# cc2530.net
KiCad netlist of a schematic drawn in Altium Designer
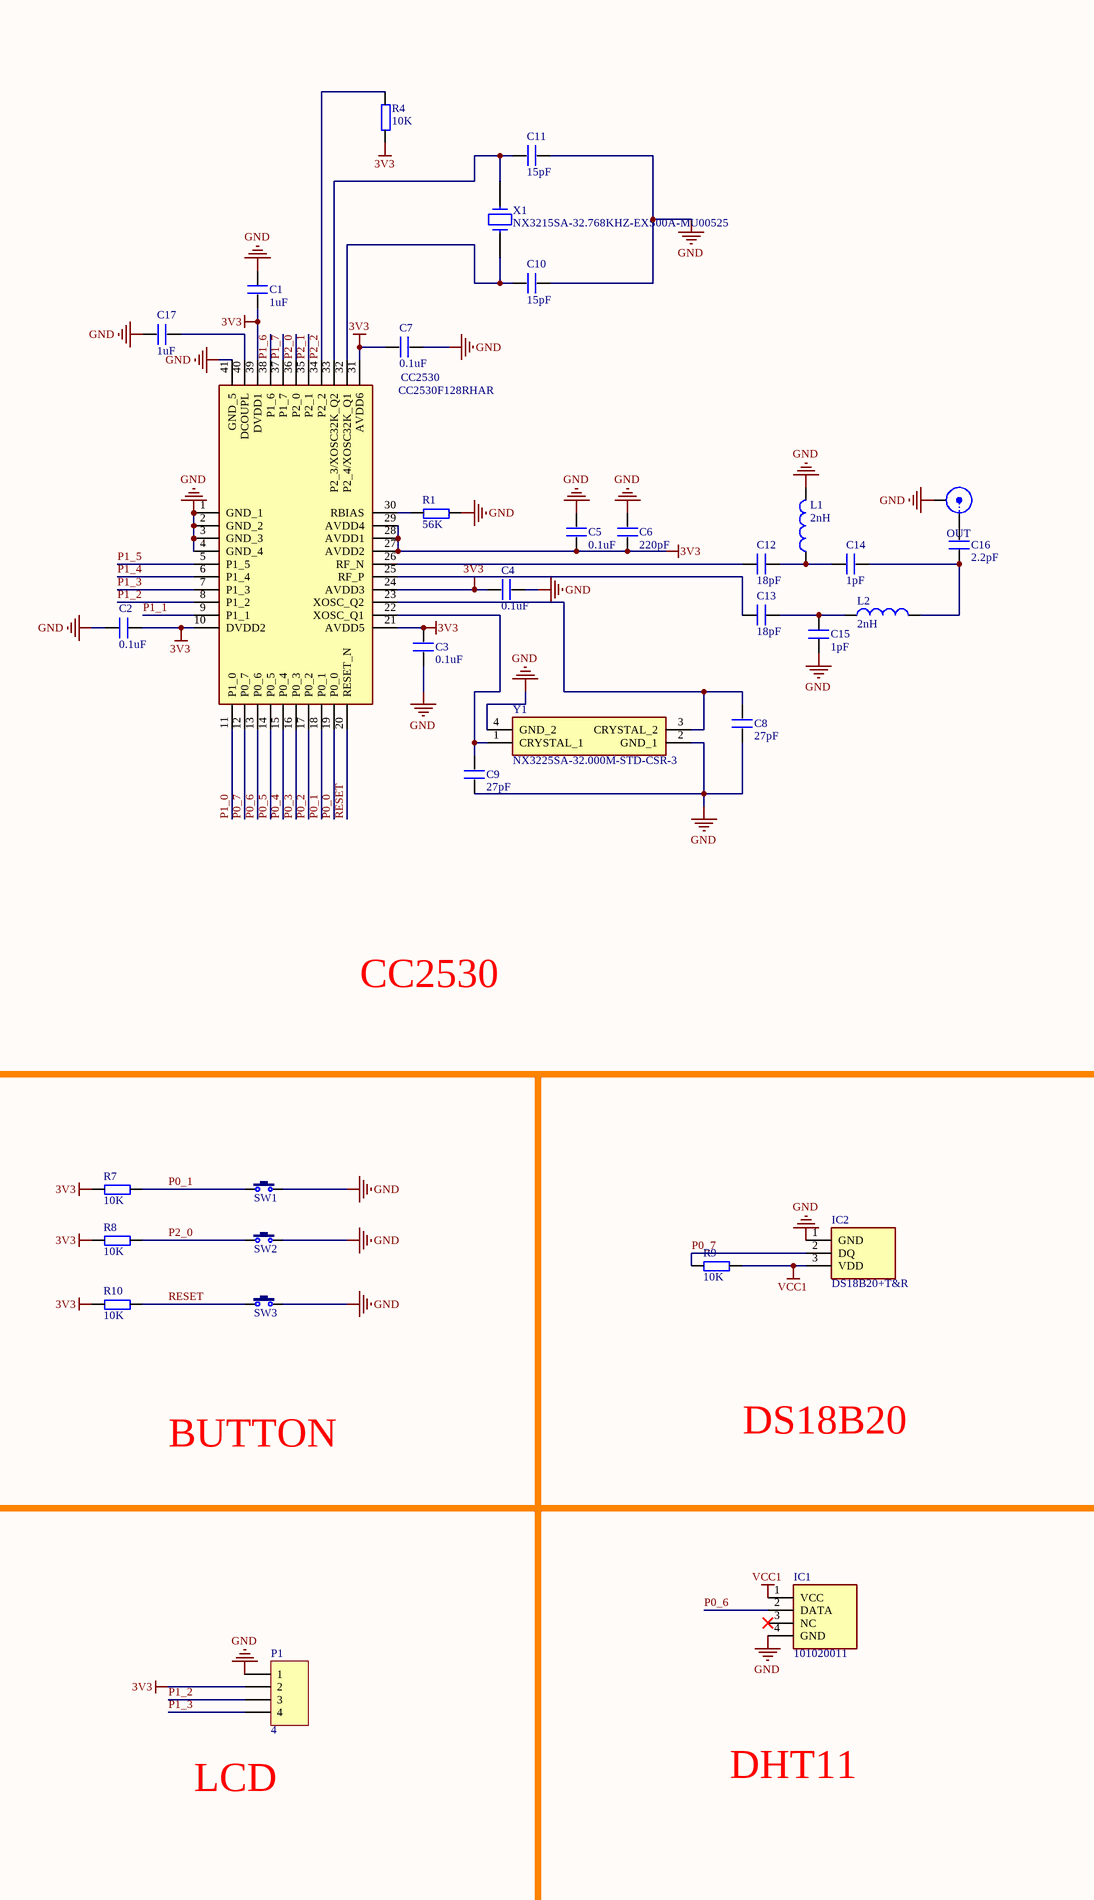
[diagram p0: cc2530.SchDoc, left]
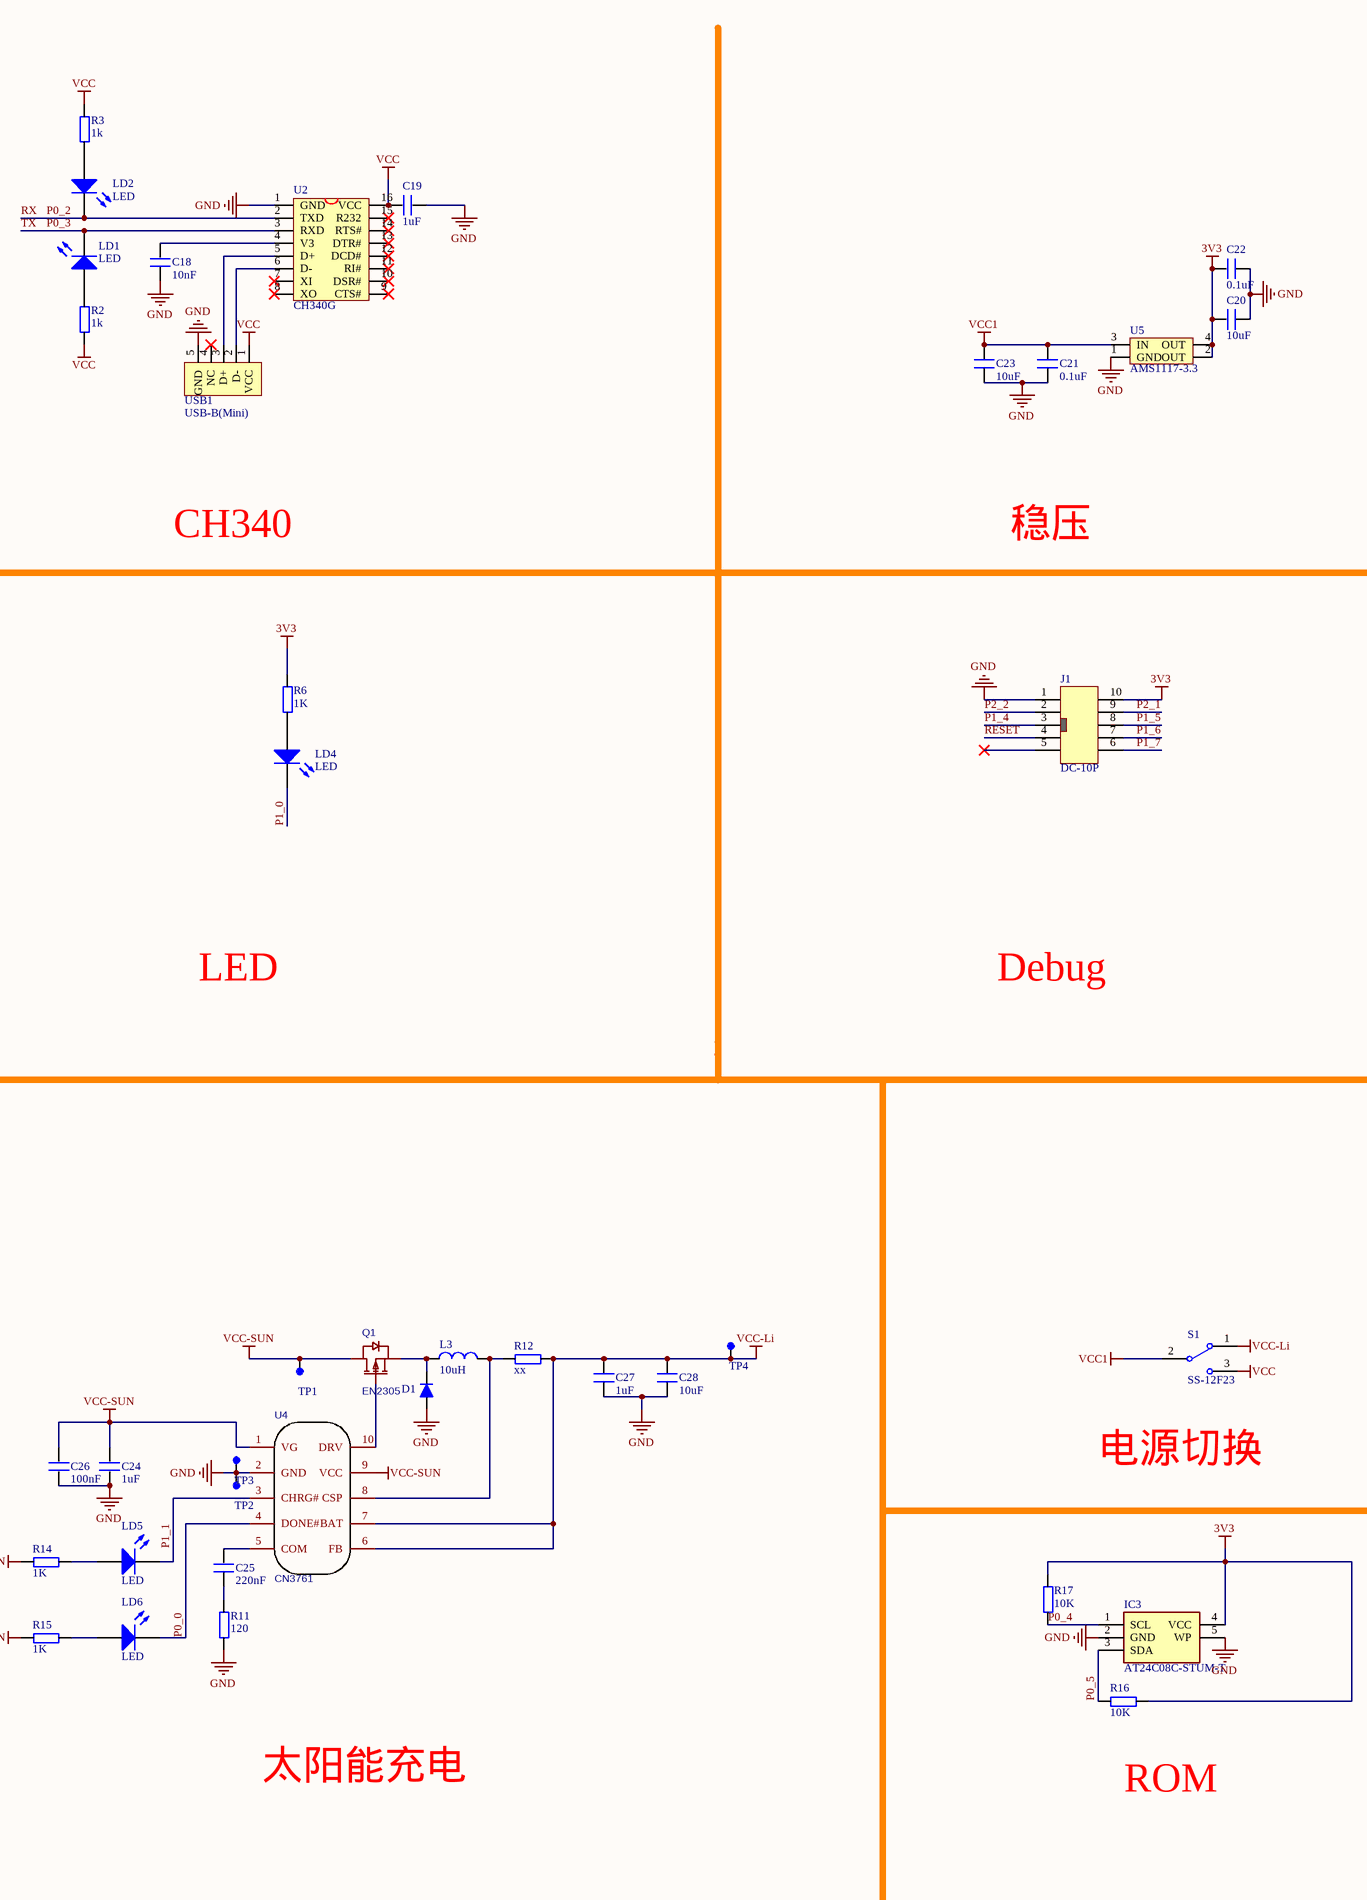
[diagram p1: cc2530.SchDoc, right]

(export (version "E")
  (design (tool "Eeschema 10.0.6"))
  (components
    (comp (ref "C1")
      (value "1uF")
      (footprint "0402")
      (description "Capacitor")
      (libsource (lib "MYLIB") (part "C"))
    )
    (comp (ref "C2")
      (value "0.1uF")
      (footprint "0402")
      (description "Capacitor")
      (libsource (lib "MYLIB") (part "C"))
    )
    (comp (ref "C3")
      (value "0.1uF")
      (footprint "0402")
      (description "Capacitor")
      (libsource (lib "MYLIB") (part "C"))
    )
    (comp (ref "C4")
      (value "0.1uF")
      (footprint "0402")
      (description "Capacitor")
      (libsource (lib "MYLIB") (part "C"))
    )
    (comp (ref "C5")
      (value "0.1uF")
      (footprint "0402")
      (description "Capacitor")
      (libsource (lib "MYLIB") (part "C"))
    )
    (comp (ref "C6")
      (value "220pF")
      (footprint "0402")
      (description "Capacitor")
      (libsource (lib "MYLIB") (part "C"))
    )
    (comp (ref "C7")
      (value "0.1uF")
      (footprint "0402")
      (description "Capacitor")
      (libsource (lib "MYLIB") (part "C"))
    )
    (comp (ref "C8")
      (value "27pF")
      (footprint "0603C")
      (description "Capacitor")
      (libsource (lib "MYLIB") (part "C"))
    )
    (comp (ref "C9")
      (value "27pF")
      (footprint "0603C")
      (description "Capacitor")
      (libsource (lib "MYLIB") (part "C"))
    )
    (comp (ref "C10")
      (value "15pF")
      (footprint "0603C")
      (description "Capacitor")
      (libsource (lib "MYLIB") (part "C"))
    )
    (comp (ref "C11")
      (value "15pF")
      (footprint "0603C")
      (description "Capacitor")
      (libsource (lib "MYLIB") (part "C"))
    )
    (comp (ref "C12")
      (value "18pF")
      (footprint "0402")
      (description "Capacitor")
      (libsource (lib "MYLIB") (part "C"))
    )
    (comp (ref "C13")
      (value "18pF")
      (footprint "0402")
      (description "Capacitor")
      (libsource (lib "MYLIB") (part "C"))
    )
    (comp (ref "C14")
      (value "1pF")
      (footprint "0402")
      (description "Capacitor")
      (libsource (lib "MYLIB") (part "C"))
    )
    (comp (ref "C15")
      (value "1pF")
      (footprint "0402")
      (description "Capacitor")
      (libsource (lib "MYLIB") (part "C"))
    )
    (comp (ref "C16")
      (value "2.2pF")
      (footprint "0402")
      (description "Capacitor")
      (libsource (lib "MYLIB") (part "C"))
    )
    (comp (ref "C17")
      (value "1uF")
      (footprint "0402")
      (description "Capacitor")
      (libsource (lib "MYLIB") (part "C"))
    )
    (comp (ref "C18")
      (value "10nF")
      (footprint "0603C")
      (description "Capacitor")
      (libsource (lib "MYLIB") (part "C"))
    )
    (comp (ref "C19")
      (value "1uF")
      (footprint "0603C")
      (description "Capacitor")
      (libsource (lib "MYLIB") (part "C"))
    )
    (comp (ref "C20")
      (value "10uF")
      (footprint "0603C")
      (description "Capacitor")
      (libsource (lib "MYLIB") (part "C"))
    )
    (comp (ref "C21")
      (value "0.1uF")
      (footprint "0603C")
      (description "Capacitor")
      (libsource (lib "MYLIB") (part "C"))
    )
    (comp (ref "C22")
      (value "0.1uF")
      (footprint "0603C")
      (description "Capacitor")
      (libsource (lib "MYLIB") (part "C"))
    )
    (comp (ref "C23")
      (value "10uF")
      (footprint "0603C")
      (description "Capacitor")
      (libsource (lib "MYLIB") (part "C"))
    )
    (comp (ref "C24")
      (value "1uF")
      (footprint "0603C")
      (description "Capacitor")
      (libsource (lib "MYLIB") (part "C"))
    )
    (comp (ref "C25")
      (value "220nF")
      (footprint "0603C")
      (description "Capacitor")
      (libsource (lib "MYLIB") (part "C"))
    )
    (comp (ref "C26")
      (value "100nF")
      (footprint "0603C")
      (description "Capacitor")
      (libsource (lib "MYLIB") (part "C"))
    )
    (comp (ref "C27")
      (value "1uF")
      (footprint "0603C")
      (description "Capacitor")
      (libsource (lib "MYLIB") (part "C"))
    )
    (comp (ref "C28")
      (value "10uF")
      (footprint "0603C")
      (description "Capacitor")
      (libsource (lib "MYLIB") (part "C"))
    )
    (comp (ref "CC2530")
      (value "CC2530F128RHAR")
      (footprint "MYLIB:QFN50P600X600X100-41N-D")
      (description "Integrated Circuit")
      (fields (field (name "MOUSER PART NUMBER") "595-CC2530F128RHAR"))
      (libsource (lib "*") (part "CC2530F128RHAR"))
    )
    (comp (ref "D1")
      (value "D")
      (footprint "D-SMA")
      (description "二极管")
      (libsource (lib "xuxuxu") (part "Diode"))
    )
    (comp (ref "IC1")
      (value "101020011")
      (footprint "MYLIB:HDRV4W80P0X254_1X4_1200X500X1550P")
      (description "Integrated Circuit")
      (fields (field (name "MOUSER PART NUMBER") "713-101020011"))
      (libsource (lib "*") (part "101020011"))
    )
    (comp (ref "IC2")
      (value "DS18B20+T&R")
      (footprint "MYLIB:DS18B20TR")
      (description "Integrated Circuit")
      (fields (field (name "MOUSER PART NUMBER") "700-DS18B20T&R"))
      (libsource (lib "*") (part "DS18B20+T&R"))
    )
    (comp (ref "IC3")
      (value "AT24C08C-STUM-T")
      (footprint "MYLIB:SOT95P280X100-5N")
      (description "Integrated Circuit")
      (fields (field (name "MOUSER PART NUMBER") "556-AT24C08C-STUM-T"))
      (libsource (lib "*") (part "AT24C08C-STUM-T"))
    )
    (comp (ref "J1") (value "DC-10P") (footprint "DC-10P") (libsource (lib "xuxuxu") (part "DC-10P")))
    (comp (ref "L1")
      (value "2nH")
      (footprint "0402")
      (description "Inductor")
      (fields (field (name "PUBLISHER") "Altium Limited"))
      (libsource (lib "MYLIB") (part "Inductor"))
    )
    (comp (ref "L2")
      (value "2nH")
      (footprint "0402")
      (description "Inductor")
      (fields (field (name "PUBLISHER") "Altium Limited"))
      (libsource (lib "MYLIB") (part "Inductor"))
    )
    (comp (ref "L3") (value "10uH") (footprint "L-6.5mm") (libsource (lib "xuxuxu") (part "Inductor")))
    (comp (ref "LD1")
      (value "LED")
      (footprint "SMDLED")
      (description "Typical RED, GREEN, YELLOW, AMBER GaAs LED")
      (fields (field (name "PUBLISHER") "Altium Limited"))
      (libsource (lib "MYLIB") (part "LED"))
    )
    (comp (ref "LD2")
      (value "LED")
      (footprint "SMDLED")
      (description "Typical RED, GREEN, YELLOW, AMBER GaAs LED")
      (fields (field (name "PUBLISHER") "Altium Limited"))
      (libsource (lib "MYLIB") (part "LED"))
    )
    (comp (ref "LD4")
      (value "LED")
      (footprint "SMDLED")
      (description "Typical RED, GREEN, YELLOW, AMBER GaAs LED")
      (fields (field (name "PUBLISHER") "Altium Limited"))
      (libsource (lib "MYLIB") (part "LED"))
    )
    (comp (ref "LD5")
      (value "LED")
      (footprint "SMDLED")
      (description "Typical RED, GREEN, YELLOW, AMBER GaAs LED")
      (fields (field (name "PUBLISHER") "Altium Limited"))
      (libsource (lib "MYLIB") (part "LED"))
    )
    (comp (ref "LD6")
      (value "LED")
      (footprint "SMDLED")
      (description "Typical RED, GREEN, YELLOW, AMBER GaAs LED")
      (fields (field (name "PUBLISHER") "Altium Limited"))
      (libsource (lib "MYLIB") (part "LED"))
    )
    (comp (ref "OUT")
      (value "SMA")
      (footprint "SMA")
      (description "SMA Connector")
      (libsource (lib "MYLIB") (part "SMA"))
    )
    (comp (ref "P1")
      (value "4")
      (footprint "HDR1X4")
      (description "Header, 4-Pin")
      (fields (field (name "PUBLISHER") "Altium Limited"))
      (libsource (lib "MYLIB") (part "Header 4"))
    )
    (comp (ref "Q1")
      (value "EN2305")
      (footprint "CN2305")
      (fields (field (name "BOM_SUPPLIER PART") "C967035") (field (name "CONTRIBUTOR") "LCSC"))
      (libsource (lib "MYLIB") (part "EN2305"))
    )
    (comp (ref "R1")
      (value "56K")
      (footprint "0402")
      (description "Resistor")
      (libsource (lib "MYLIB") (part "Resistor"))
    )
    (comp (ref "R2")
      (value "1k")
      (footprint "0603R")
      (description "Resistor")
      (libsource (lib "MYLIB") (part "Resistor"))
    )
    (comp (ref "R3")
      (value "1k")
      (footprint "0603R")
      (description "Resistor")
      (libsource (lib "MYLIB") (part "Resistor"))
    )
    (comp (ref "R4")
      (value "10K")
      (footprint "0603R")
      (description "Resistor")
      (libsource (lib "MYLIB") (part "Resistor"))
    )
    (comp (ref "R6")
      (value "1K")
      (footprint "0603R")
      (description "Resistor")
      (libsource (lib "MYLIB") (part "Resistor"))
    )
    (comp (ref "R7")
      (value "10K")
      (footprint "0603R")
      (description "Resistor")
      (libsource (lib "MYLIB") (part "Resistor"))
    )
    (comp (ref "R8")
      (value "10K")
      (footprint "0603R")
      (description "Resistor")
      (libsource (lib "MYLIB") (part "Resistor"))
    )
    (comp (ref "R9")
      (value "10K")
      (footprint "0603R")
      (description "Resistor")
      (libsource (lib "MYLIB") (part "Resistor"))
    )
    (comp (ref "R10")
      (value "10K")
      (footprint "0603R")
      (description "Resistor")
      (libsource (lib "MYLIB") (part "Resistor"))
    )
    (comp (ref "R11")
      (value "120")
      (footprint "0603R")
      (description "Resistor")
      (libsource (lib "MYLIB") (part "Resistor"))
    )
    (comp (ref "R12")
      (value "xx")
      (footprint "0603R")
      (description "Resistor")
      (libsource (lib "MYLIB") (part "Resistor"))
    )
    (comp (ref "R14")
      (value "1K")
      (footprint "0402")
      (description "Resistor")
      (libsource (lib "MYLIB") (part "Resistor"))
    )
    (comp (ref "R15")
      (value "1K")
      (footprint "0402")
      (description "Resistor")
      (libsource (lib "MYLIB") (part "Resistor"))
    )
    (comp (ref "R16")
      (value "10K")
      (footprint "0603R")
      (description "Resistor")
      (libsource (lib "MYLIB") (part "Resistor"))
    )
    (comp (ref "R17")
      (value "10K")
      (footprint "0603R")
      (description "Resistor")
      (libsource (lib "MYLIB") (part "Resistor"))
    )
    (comp (ref "S1")
      (value "SS-12F23")
      (footprint "MSK-12C01-07")
      (description "1路波动开关")
      (fields (field (name "版权归属") "源创客"))
      (libsource (lib "MYLIB") (part "SSW-1P"))
    )
    (comp (ref "SW1")
      (value "3x6x5")
      (footprint "TSW SMD-3*6*2.5")
      (description "3x6轻触开关")
      (fields (field (name "版权归属") "源创客"))
      (libsource (lib "MYLIB") (part "TSW 3x6"))
    )
    (comp (ref "SW2")
      (value "3x6x5")
      (footprint "TSW SMD-3*6*2.5")
      (description "3x6轻触开关")
      (fields (field (name "版权归属") "源创客"))
      (libsource (lib "MYLIB") (part "TSW 3x6"))
    )
    (comp (ref "SW3")
      (value "3x6x5")
      (footprint "TSW SMD-3*6*2.5")
      (description "3x6轻触开关")
      (fields (field (name "版权归属") "源创客"))
      (libsource (lib "MYLIB") (part "TSW 3x6"))
    )
    (comp (ref "TP1") (value "test point") (footprint "TP") (libsource (lib "xuxuxu") (part "TP")))
    (comp (ref "TP2") (value "test point") (footprint "TP") (libsource (lib "xuxuxu") (part "TP")))
    (comp (ref "TP3") (value "test point") (footprint "TP") (libsource (lib "xuxuxu") (part "TP")))
    (comp (ref "TP4") (value "test point") (footprint "TP") (libsource (lib "xuxuxu") (part "TP")))
    (comp (ref "U2")
      (value "CH340G")
      (footprint "SOP16M")
      (description "USB2UART")
      (libsource (lib "MYLIB") (part "CH340G"))
    )
    (comp (ref "U4")
      (value "CN3761")
      (footprint "CN3761")
      (fields (field (name "BOM_SUPPLIER PART") "C41308"))
      (libsource (lib "MYLIB") (part "CN3761_1"))
    )
    (comp (ref "U5") (value "AMS1117-3.3") (footprint "AMS1117") (libsource (lib "MYLIB") (part "AMS1117")))
    (comp (ref "USB1")
      (value "USB-B(Mini)")
      (footprint "USB/SM0.8-6H5")
      (libsource (lib "MYLIB") (part "USB5_1"))
    )
    (comp (ref "X1")
      (value "NX3215SA-32.768KHZ-EXS00A-MU00525")
      (footprint "XTAL_2SM_3R2X1R5")
      (description "Crystal")
      (libsource (lib "MYLIB") (part "XTAL"))
    )
    (comp (ref "Y1")
      (value "NX3225SA-32.000M-STD-CSR-3")
      (footprint "MYLIB:NX3225SA12000MSTDCSR3")
      (description "Crystal or Oscillator")
      (fields (field (name "MANUFACTURER_PART_NUMBER") "NX3225SA-12.000M-STD-CSR-3"))
      (libsource (lib "*") (part "NX3225SA-12.000M-STD-CSR-3"))
    )
  )
  (nets
    (net (code "1") (name "/P0_0") (class "Default")
      (node (ref "CC2530") (pin "19") (pinfunction "P0_0_19") (pintype "passive"))
      (node (ref "LD6") (pin "2") (pinfunction "K_2") (pintype "passive"))
      (node (ref "U4") (pin "4") (pinfunction "DONE#_4") (pintype "passive"))
    )
    (net (code "2") (name "/P0_1") (class "Default")
      (node (ref "CC2530") (pin "18") (pinfunction "P0_1_18") (pintype "passive"))
      (node (ref "R7") (pin "2") (pintype "passive"))
      (node (ref "SW1") (pin "1") (pinfunction "1_1") (pintype "passive"))
    )
    (net (code "3") (name "/P0_2") (class "Default")
      (node (ref "CC2530") (pin "17") (pinfunction "P0_2_17") (pintype "passive"))
      (node (ref "LD2") (pin "2") (pinfunction "K_2") (pintype "passive"))
      (node (ref "U2") (pin "2") (pinfunction "TXD_2") (pintype "passive"))
    )
    (net (code "4") (name "/P0_3") (class "Default")
      (node (ref "CC2530") (pin "16") (pinfunction "P0_3_16") (pintype "passive"))
      (node (ref "LD1") (pin "2") (pinfunction "K_2") (pintype "passive"))
      (node (ref "U2") (pin "3") (pinfunction "RXD_3") (pintype "passive"))
    )
    (net (code "5") (name "/P0_4") (class "Default")
      (node (ref "CC2530") (pin "15") (pinfunction "P0_4_15") (pintype "passive"))
      (node (ref "IC3") (pin "1") (pinfunction "SCL_1") (pintype "passive"))
      (node (ref "R17") (pin "1") (pintype "passive"))
    )
    (net (code "6") (name "/P0_5") (class "Default")
      (node (ref "CC2530") (pin "14") (pinfunction "P0_5_14") (pintype "passive"))
      (node (ref "IC3") (pin "3") (pinfunction "SDA_3") (pintype "passive"))
      (node (ref "R16") (pin "1") (pintype "passive"))
    )
    (net (code "7") (name "/P0_6") (class "Default")
      (node (ref "CC2530") (pin "13") (pinfunction "P0_6_13") (pintype "passive"))
      (node (ref "IC1") (pin "2") (pinfunction "DATA_2") (pintype "passive"))
    )
    (net (code "8") (name "/P0_7") (class "Default")
      (node (ref "CC2530") (pin "12") (pinfunction "P0_7_12") (pintype "passive"))
      (node (ref "IC2") (pin "2") (pinfunction "DQ_2") (pintype "passive"))
      (node (ref "R9") (pin "1") (pintype "passive"))
    )
    (net (code "9") (name "/P1_0") (class "Default")
      (node (ref "CC2530") (pin "11") (pinfunction "P1_0_11") (pintype "passive"))
      (node (ref "LD4") (pin "2") (pinfunction "K_2") (pintype "passive"))
    )
    (net (code "10") (name "/P1_1") (class "Default")
      (node (ref "CC2530") (pin "9") (pinfunction "P1_1_9") (pintype "passive"))
      (node (ref "LD5") (pin "2") (pinfunction "K_2") (pintype "passive"))
      (node (ref "U4") (pin "3") (pinfunction "CHRG#_3") (pintype "passive"))
    )
    (net (code "11") (name "/P1_2") (class "Default")
      (node (ref "CC2530") (pin "8") (pinfunction "P1_2_8") (pintype "passive"))
      (node (ref "P1") (pin "3") (pinfunction "3_3") (pintype "passive"))
    )
    (net (code "12") (name "/P1_3") (class "Default")
      (node (ref "CC2530") (pin "7") (pinfunction "P1_3_7") (pintype "passive"))
      (node (ref "P1") (pin "4") (pinfunction "4_4") (pintype "passive"))
    )
    (net (code "13") (name "/P1_4") (class "Default")
      (node (ref "CC2530") (pin "6") (pinfunction "P1_4_6") (pintype "passive"))
      (node (ref "J1") (pin "3") (pinfunction "3_3") (pintype "passive"))
    )
    (net (code "14") (name "/P1_5") (class "Default")
      (node (ref "CC2530") (pin "5") (pinfunction "P1_5_5") (pintype "passive"))
      (node (ref "J1") (pin "8") (pinfunction "8_8") (pintype "passive"))
    )
    (net (code "15") (name "/P1_6") (class "Default")
      (node (ref "CC2530") (pin "38") (pinfunction "P1_6_38") (pintype "passive"))
      (node (ref "J1") (pin "7") (pinfunction "7_7") (pintype "passive"))
    )
    (net (code "16") (name "/P1_7") (class "Default")
      (node (ref "CC2530") (pin "37") (pinfunction "P1_7_37") (pintype "passive"))
      (node (ref "J1") (pin "6") (pinfunction "6_6") (pintype "passive"))
    )
    (net (code "17") (name "/P2_0") (class "Default")
      (node (ref "CC2530") (pin "36") (pinfunction "P2_0_36") (pintype "passive"))
      (node (ref "R8") (pin "2") (pintype "passive"))
      (node (ref "SW2") (pin "1") (pinfunction "1_1") (pintype "passive"))
    )
    (net (code "18") (name "/P2_1") (class "Default")
      (node (ref "CC2530") (pin "35") (pinfunction "P2_1_35") (pintype "passive"))
      (node (ref "J1") (pin "9") (pinfunction "9_9") (pintype "passive"))
    )
    (net (code "19") (name "/P2_2") (class "Default")
      (node (ref "CC2530") (pin "34") (pinfunction "P2_2_34") (pintype "passive"))
      (node (ref "J1") (pin "2") (pinfunction "2_2") (pintype "passive"))
      (node (ref "R4") (pin "2") (pintype "passive"))
    )
    (net (code "20") (name "/RESET") (class "Default")
      (node (ref "CC2530") (pin "20") (pinfunction "RESET_N_20") (pintype "passive"))
      (node (ref "J1") (pin "4") (pinfunction "4_4") (pintype "passive"))
      (node (ref "R10") (pin "2") (pintype "passive"))
      (node (ref "SW3") (pin "1") (pinfunction "1_1") (pintype "passive"))
    )
    (net (code "21") (name "3V3") (class "Default")
      (node (ref "C1") (pin "1") (pintype "passive"))
      (node (ref "C2") (pin "2") (pintype "passive"))
      (node (ref "C20") (pin "2") (pintype "passive"))
      (node (ref "C22") (pin "2") (pintype "passive"))
      (node (ref "C3") (pin "1") (pintype "passive"))
      (node (ref "C4") (pin "1") (pintype "passive"))
      (node (ref "C5") (pin "1") (pintype "passive"))
      (node (ref "C6") (pin "1") (pintype "passive"))
      (node (ref "C7") (pin "1") (pintype "passive"))
      (node (ref "CC2530") (pin "10") (pinfunction "DVDD2_10") (pintype "passive"))
      (node (ref "CC2530") (pin "21") (pinfunction "AVDD5_21") (pintype "passive"))
      (node (ref "CC2530") (pin "24") (pinfunction "AVDD3_24") (pintype "passive"))
      (node (ref "CC2530") (pin "27") (pinfunction "AVDD2_27") (pintype "passive"))
      (node (ref "CC2530") (pin "28") (pinfunction "AVDD1_28") (pintype "passive"))
      (node (ref "CC2530") (pin "29") (pinfunction "AVDD4_29") (pintype "passive"))
      (node (ref "CC2530") (pin "31") (pinfunction "AVDD6_31") (pintype "passive"))
      (node (ref "CC2530") (pin "39") (pinfunction "DVDD1_39") (pintype "passive"))
      (node (ref "IC3") (pin "4") (pinfunction "VCC_4") (pintype "passive"))
      (node (ref "J1") (pin "10") (pinfunction "10_10") (pintype "passive"))
      (node (ref "P1") (pin "2") (pinfunction "2_2") (pintype "passive"))
      (node (ref "R10") (pin "1") (pintype "passive"))
      (node (ref "R16") (pin "2") (pintype "passive"))
      (node (ref "R17") (pin "2") (pintype "passive"))
      (node (ref "R4") (pin "1") (pintype "passive"))
      (node (ref "R6") (pin "2") (pintype "passive"))
      (node (ref "R7") (pin "1") (pintype "passive"))
      (node (ref "R8") (pin "1") (pintype "passive"))
      (node (ref "U5") (pin "2") (pinfunction "OUT_2") (pintype "passive"))
      (node (ref "U5") (pin "4") (pinfunction "OUT_4") (pintype "passive"))
    )
    (net (code "22") (name "GND") (class "Default")
      (node (ref "C1") (pin "2") (pintype "passive"))
      (node (ref "C10") (pin "2") (pintype "passive"))
      (node (ref "C11") (pin "2") (pintype "passive"))
      (node (ref "C15") (pin "1") (pintype "passive"))
      (node (ref "C17") (pin "1") (pintype "passive"))
      (node (ref "C18") (pin "1") (pintype "passive"))
      (node (ref "C19") (pin "2") (pintype "passive"))
      (node (ref "C2") (pin "1") (pintype "passive"))
      (node (ref "C20") (pin "1") (pintype "passive"))
      (node (ref "C21") (pin "1") (pintype "passive"))
      (node (ref "C22") (pin "1") (pintype "passive"))
      (node (ref "C23") (pin "2") (pintype "passive"))
      (node (ref "C24") (pin "1") (pintype "passive"))
      (node (ref "C26") (pin "1") (pintype "passive"))
      (node (ref "C27") (pin "1") (pintype "passive"))
      (node (ref "C28") (pin "1") (pintype "passive"))
      (node (ref "C3") (pin "2") (pintype "passive"))
      (node (ref "C4") (pin "2") (pintype "passive"))
      (node (ref "C5") (pin "2") (pintype "passive"))
      (node (ref "C6") (pin "2") (pintype "passive"))
      (node (ref "C7") (pin "2") (pintype "passive"))
      (node (ref "C8") (pin "1") (pintype "passive"))
      (node (ref "C9") (pin "1") (pintype "passive"))
      (node (ref "CC2530") (pin "1") (pinfunction "GND_1_1") (pintype "passive"))
      (node (ref "CC2530") (pin "2") (pinfunction "GND_2_2") (pintype "passive"))
      (node (ref "CC2530") (pin "3") (pinfunction "GND_3_3") (pintype "passive"))
      (node (ref "CC2530") (pin "4") (pinfunction "GND_4_4") (pintype "passive"))
      (node (ref "CC2530") (pin "41") (pinfunction "GND_5_41") (pintype "passive"))
      (node (ref "D1") (pin "1") (pinfunction "1_1") (pintype "passive"))
      (node (ref "IC1") (pin "4") (pinfunction "GND_4") (pintype "passive"))
      (node (ref "IC2") (pin "1") (pinfunction "GND_1") (pintype "passive"))
      (node (ref "IC3") (pin "2") (pinfunction "GND_2") (pintype "passive"))
      (node (ref "IC3") (pin "5") (pinfunction "WP_5") (pintype "passive"))
      (node (ref "J1") (pin "1") (pinfunction "1_1") (pintype "passive"))
      (node (ref "L1") (pin "2") (pinfunction "2_2") (pintype "passive"))
      (node (ref "OUT") (pin "2") (pinfunction "Y_2") (pintype "passive"))
      (node (ref "P1") (pin "1") (pinfunction "1_1") (pintype "passive"))
      (node (ref "R1") (pin "2") (pintype "passive"))
      (node (ref "R11") (pin "1") (pintype "passive"))
      (node (ref "SW1") (pin "2") (pinfunction "2_2") (pintype "passive"))
      (node (ref "SW2") (pin "2") (pinfunction "2_2") (pintype "passive"))
      (node (ref "SW3") (pin "2") (pinfunction "2_2") (pintype "passive"))
      (node (ref "TP2") (pin "1") (pinfunction "1_1") (pintype "passive"))
      (node (ref "TP3") (pin "1") (pinfunction "1_1") (pintype "passive"))
      (node (ref "U2") (pin "1") (pinfunction "GND_1") (pintype "passive"))
      (node (ref "U4") (pin "2") (pinfunction "GND_2") (pintype "passive"))
      (node (ref "U5") (pin "1") (pinfunction "GND_1") (pintype "passive"))
      (node (ref "USB1") (pin "5") (pinfunction "GND_5") (pintype "passive"))
      (node (ref "Y1") (pin "2") (pinfunction "GND_1_2") (pintype "passive"))
      (node (ref "Y1") (pin "4") (pinfunction "GND_2_4") (pintype "passive"))
    )
    (net (code "23") (name "Net-(C12-Pad2)") (class "Default")
      (node (ref "C12") (pin "2") (pintype "passive"))
      (node (ref "C14") (pin "1") (pintype "passive"))
      (node (ref "L1") (pin "1") (pinfunction "1_1") (pintype "passive"))
    )
    (net (code "24") (name "Net-(C13-Pad2)") (class "Default")
      (node (ref "C13") (pin "2") (pintype "passive"))
      (node (ref "C15") (pin "2") (pintype "passive"))
      (node (ref "L2") (pin "1") (pinfunction "1_1") (pintype "passive"))
    )
    (net (code "25") (name "Net-(C14-Pad2)") (class "Default")
      (node (ref "C14") (pin "2") (pintype "passive"))
      (node (ref "C16") (pin "1") (pintype "passive"))
      (node (ref "L2") (pin "2") (pinfunction "2_2") (pintype "passive"))
    )
    (net (code "26") (name "Net-(C25-Pad1)") (class "Default")
      (node (ref "C25") (pin "1") (pintype "passive"))
      (node (ref "R11") (pin "2") (pintype "passive"))
    )
    (net (code "27") (name "Net-(CC2530-DCOUPL)") (class "Default")
      (node (ref "C17") (pin "2") (pintype "passive"))
      (node (ref "CC2530") (pin "40") (pinfunction "DCOUPL_40") (pintype "passive"))
    )
    (net (code "28") (name "Net-(CC2530-P2_3{slash}XOSC32K_Q2)") (class "Default")
      (node (ref "C11") (pin "1") (pintype "passive"))
      (node (ref "CC2530") (pin "33") (pinfunction "P2_3/XOSC32K_Q2_33") (pintype "passive"))
      (node (ref "X1") (pin "1") (pinfunction "1_1") (pintype "passive"))
    )
    (net (code "29") (name "Net-(CC2530-P2_4{slash}XOSC32K_Q1)") (class "Default")
      (node (ref "C10") (pin "1") (pintype "passive"))
      (node (ref "CC2530") (pin "32") (pinfunction "P2_4/XOSC32K_Q1_32") (pintype "passive"))
      (node (ref "X1") (pin "2") (pinfunction "2_2") (pintype "passive"))
    )
    (net (code "30") (name "Net-(CC2530-RBIAS)") (class "Default")
      (node (ref "CC2530") (pin "30") (pinfunction "RBIAS_30") (pintype "passive"))
      (node (ref "R1") (pin "1") (pintype "passive"))
    )
    (net (code "31") (name "Net-(CC2530-RF_N)") (class "Default")
      (node (ref "C12") (pin "1") (pintype "passive"))
      (node (ref "CC2530") (pin "26") (pinfunction "RF_N_26") (pintype "passive"))
    )
    (net (code "32") (name "Net-(CC2530-RF_P)") (class "Default")
      (node (ref "C13") (pin "1") (pintype "passive"))
      (node (ref "CC2530") (pin "25") (pinfunction "RF_P_25") (pintype "passive"))
    )
    (net (code "33") (name "Net-(CC2530-XOSC_Q1)") (class "Default")
      (node (ref "C9") (pin "2") (pintype "passive"))
      (node (ref "CC2530") (pin "22") (pinfunction "XOSC_Q1_22") (pintype "passive"))
      (node (ref "Y1") (pin "1") (pinfunction "CRYSTAL_1_1") (pintype "passive"))
    )
    (net (code "34") (name "Net-(CC2530-XOSC_Q2)") (class "Default")
      (node (ref "C8") (pin "2") (pintype "passive"))
      (node (ref "CC2530") (pin "23") (pinfunction "XOSC_Q2_23") (pintype "passive"))
      (node (ref "Y1") (pin "3") (pinfunction "CRYSTAL_2_3") (pintype "passive"))
    )
    (net (code "35") (name "Net-(LD1-A)") (class "Default")
      (node (ref "LD1") (pin "1") (pinfunction "A_1") (pintype "passive"))
      (node (ref "R2") (pin "2") (pintype "passive"))
    )
    (net (code "36") (name "Net-(LD2-A)") (class "Default")
      (node (ref "LD2") (pin "1") (pinfunction "A_1") (pintype "passive"))
      (node (ref "R3") (pin "1") (pintype "passive"))
    )
    (net (code "37") (name "Net-(LD4-A)") (class "Default")
      (node (ref "LD4") (pin "1") (pinfunction "A_1") (pintype "passive"))
      (node (ref "R6") (pin "1") (pintype "passive"))
    )
    (net (code "38") (name "Net-(LD5-A)") (class "Default")
      (node (ref "LD5") (pin "1") (pinfunction "A_1") (pintype "passive"))
      (node (ref "R14") (pin "2") (pintype "passive"))
    )
    (net (code "39") (name "Net-(LD6-A)") (class "Default")
      (node (ref "LD6") (pin "1") (pinfunction "A_1") (pintype "passive"))
      (node (ref "R15") (pin "2") (pintype "passive"))
    )
    (net (code "40") (name "Net-(OUT-X)") (class "Default")
      (node (ref "C16") (pin "2") (pintype "passive"))
      (node (ref "OUT") (pin "1") (pinfunction "X_1") (pintype "passive"))
    )
    (net (code "41") (name "Net-(Q1-G)") (class "Default")
      (node (ref "Q1") (pin "1") (pinfunction "G_1") (pintype "passive"))
      (node (ref "U4") (pin "10") (pinfunction "DRV_10") (pintype "passive"))
    )
    (net (code "42") (name "Net-(Q1-S)") (class "Default")
      (node (ref "D1") (pin "2") (pinfunction "2_2") (pintype "passive"))
      (node (ref "L3") (pin "1") (pinfunction "1_1") (pintype "passive"))
      (node (ref "Q1") (pin "2") (pinfunction "S_2") (pintype "passive"))
    )
    (net (code "43") (name "Net-(U2-D+)") (class "Default")
      (node (ref "U2") (pin "5") (pinfunction "D+_5") (pintype "passive"))
      (node (ref "USB1") (pin "3") (pinfunction "D+_3") (pintype "passive"))
    )
    (net (code "44") (name "Net-(U2-D-)") (class "Default")
      (node (ref "U2") (pin "6") (pinfunction "D-_6") (pintype "passive"))
      (node (ref "USB1") (pin "2") (pinfunction "D-_2") (pintype "passive"))
    )
    (net (code "45") (name "Net-(U2-V3)") (class "Default")
      (node (ref "C18") (pin "2") (pintype "passive"))
      (node (ref "U2") (pin "4") (pinfunction "V3_4") (pintype "passive"))
    )
    (net (code "46") (name "Net-(U4-COM)") (class "Default")
      (node (ref "C25") (pin "2") (pintype "passive"))
      (node (ref "U4") (pin "5") (pinfunction "COM_5") (pintype "passive"))
    )
    (net (code "47") (name "Net-(U4-CSP)") (class "Default")
      (node (ref "L3") (pin "2") (pinfunction "2_2") (pintype "passive"))
      (node (ref "R12") (pin "1") (pintype "passive"))
      (node (ref "U4") (pin "8") (pinfunction "CSP_8") (pintype "passive"))
    )
    (net (code "48") (name "VCC") (class "Default")
      (node (ref "C19") (pin "1") (pintype "passive"))
      (node (ref "R2") (pin "1") (pintype "passive"))
      (node (ref "R3") (pin "2") (pintype "passive"))
      (node (ref "S1") (pin "3") (pinfunction "3_3") (pintype "passive"))
      (node (ref "U2") (pin "16") (pinfunction "VCC_16") (pintype "passive"))
      (node (ref "USB1") (pin "1") (pinfunction "VCC_1") (pintype "passive"))
    )
    (net (code "49") (name "VCC-Li") (class "Default")
      (node (ref "C27") (pin "2") (pintype "passive"))
      (node (ref "C28") (pin "2") (pintype "passive"))
      (node (ref "R12") (pin "2") (pintype "passive"))
      (node (ref "S1") (pin "1") (pinfunction "1_1") (pintype "passive"))
      (node (ref "TP4") (pin "1") (pinfunction "1_1") (pintype "passive"))
      (node (ref "U4") (pin "6") (pinfunction "FB_6") (pintype "passive"))
      (node (ref "U4") (pin "7") (pinfunction "BAT_7") (pintype "passive"))
    )
    (net (code "50") (name "VCC-SUN") (class "Default")
      (node (ref "C24") (pin "2") (pintype "passive"))
      (node (ref "C26") (pin "2") (pintype "passive"))
      (node (ref "Q1") (pin "3") (pinfunction "D_3") (pintype "passive"))
      (node (ref "R14") (pin "1") (pintype "passive"))
      (node (ref "R15") (pin "1") (pintype "passive"))
      (node (ref "TP1") (pin "1") (pinfunction "1_1") (pintype "passive"))
      (node (ref "U4") (pin "1") (pinfunction "VG_1") (pintype "passive"))
      (node (ref "U4") (pin "9") (pinfunction "VCC_9") (pintype "passive"))
    )
    (net (code "51") (name "VCC1") (class "Default")
      (node (ref "C21") (pin "2") (pintype "passive"))
      (node (ref "C23") (pin "1") (pintype "passive"))
      (node (ref "IC1") (pin "1") (pinfunction "VCC_1") (pintype "passive"))
      (node (ref "IC2") (pin "3") (pinfunction "VDD_3") (pintype "passive"))
      (node (ref "R9") (pin "2") (pintype "passive"))
      (node (ref "S1") (pin "2") (pinfunction "2_2") (pintype "passive"))
      (node (ref "U5") (pin "3") (pinfunction "IN_3") (pintype "passive"))
    )
    (net (code "52") (name "unconnected-(IC1-NC-Pad3)") (class "Default")
      (node (ref "IC1") (pin "3") (pinfunction "NC_3") (pintype "passive+no_connect"))
    )
    (net (code "53") (name "unconnected-(J1-Pad5)") (class "Default")
      (node (ref "J1") (pin "5") (pinfunction "5_5") (pintype "passive+no_connect"))
    )
    (net (code "54") (name "unconnected-(U2-CTS#-Pad9)") (class "Default")
      (node (ref "U2") (pin "9") (pinfunction "CTS#_9") (pintype "passive+no_connect"))
    )
    (net (code "55") (name "unconnected-(U2-DCD#-Pad12)") (class "Default")
      (node (ref "U2") (pin "12") (pinfunction "DCD#_12") (pintype "passive+no_connect"))
    )
    (net (code "56") (name "unconnected-(U2-DSR#-Pad10)") (class "Default")
      (node (ref "U2") (pin "10") (pinfunction "DSR#_10") (pintype "passive+no_connect"))
    )
    (net (code "57") (name "unconnected-(U2-DTR#-Pad13)") (class "Default")
      (node (ref "U2") (pin "13") (pinfunction "DTR#_13") (pintype "passive+no_connect"))
    )
    (net (code "58") (name "unconnected-(U2-R232-Pad15)") (class "Default")
      (node (ref "U2") (pin "15") (pinfunction "R232_15") (pintype "passive+no_connect"))
    )
    (net (code "59") (name "unconnected-(U2-RI#-Pad11)") (class "Default")
      (node (ref "U2") (pin "11") (pinfunction "RI#_11") (pintype "passive+no_connect"))
    )
    (net (code "60") (name "unconnected-(U2-RTS#-Pad14)") (class "Default")
      (node (ref "U2") (pin "14") (pinfunction "RTS#_14") (pintype "passive+no_connect"))
    )
    (net (code "61") (name "unconnected-(U2-XI-Pad7)") (class "Default")
      (node (ref "U2") (pin "7") (pinfunction "XI_7") (pintype "passive+no_connect"))
    )
    (net (code "62") (name "unconnected-(U2-XO-Pad8)") (class "Default")
      (node (ref "U2") (pin "8") (pinfunction "XO_8") (pintype "passive+no_connect"))
    )
    (net (code "63") (name "unconnected-(USB1-NC-Pad4)") (class "Default")
      (node (ref "USB1") (pin "4") (pinfunction "NC_4") (pintype "passive+no_connect"))
    )
  )
)
